# PowerDistributionBoard.net
KiCad netlist of a schematic drawn in Altium Designer
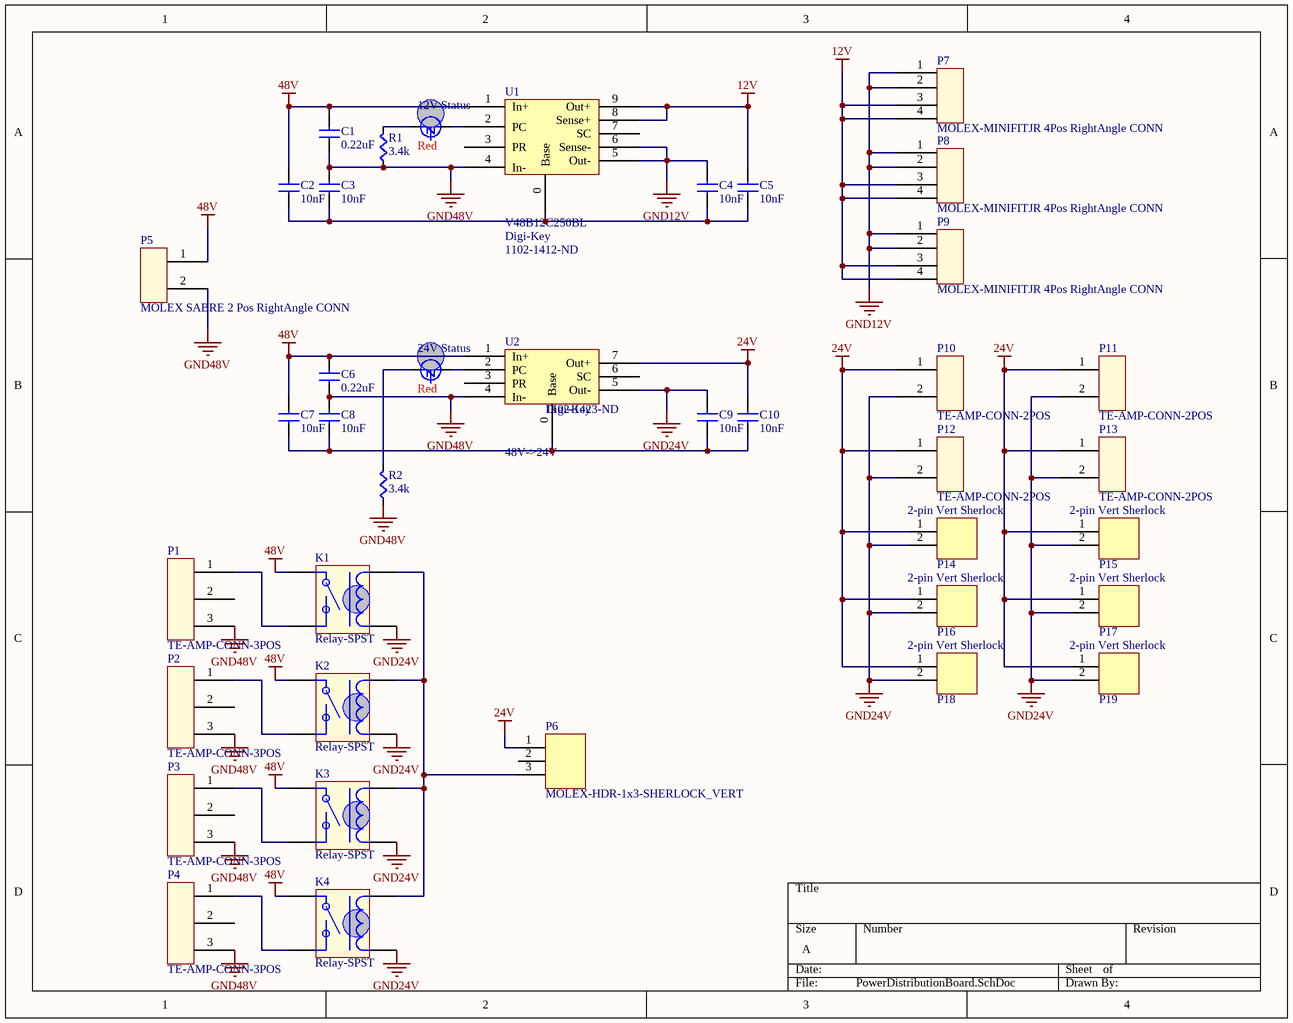
[diagram p0: PowerDistributionBoard.SchDoc]

(export (version "E")
  (design (tool "Eeschema 10.0.6"))
  (components
    (comp (ref "12V Status")
      (value "LED")
      (footprint "LED0603")
      (fields (field (name "COLOR") "Red"))
      (libsource (lib "Semiconductors") (part "LED"))
    )
    (comp (ref "24V Status")
      (value "LED")
      (footprint "LED0603")
      (fields (field (name "COLOR") "Red"))
      (libsource (lib "Semiconductors") (part "LED"))
    )
    (comp (ref "C1")
      (value "0.22uF")
      (footprint "CAP2225")
      (fields (field (name "Comment") "Cap"))
      (libsource (lib "Passives") (part "Cap"))
    )
    (comp (ref "C2")
      (value "10nF")
      (footprint "CAP2225")
      (fields (field (name "Comment") "Cap"))
      (libsource (lib "Passives") (part "Cap"))
    )
    (comp (ref "C3")
      (value "10nF")
      (footprint "CAP2225")
      (fields (field (name "Comment") "Cap"))
      (libsource (lib "Passives") (part "Cap"))
    )
    (comp (ref "C4")
      (value "10nF")
      (footprint "CAP2225")
      (fields (field (name "Comment") "Cap"))
      (libsource (lib "Passives") (part "Cap"))
    )
    (comp (ref "C5")
      (value "10nF")
      (footprint "CAP2225")
      (fields (field (name "Comment") "Cap"))
      (libsource (lib "Passives") (part "Cap"))
    )
    (comp (ref "C6")
      (value "0.22uF")
      (footprint "CAP2225")
      (fields (field (name "Comment") "Cap"))
      (libsource (lib "Passives") (part "Cap"))
    )
    (comp (ref "C7")
      (value "10nF")
      (footprint "CAP2225")
      (fields (field (name "Comment") "Cap"))
      (libsource (lib "Passives") (part "Cap"))
    )
    (comp (ref "C8")
      (value "10nF")
      (footprint "CAP2225")
      (fields (field (name "Comment") "Cap"))
      (libsource (lib "Passives") (part "Cap"))
    )
    (comp (ref "C9")
      (value "10nF")
      (footprint "CAP2225")
      (fields (field (name "Comment") "Cap"))
      (libsource (lib "Passives") (part "Cap"))
    )
    (comp (ref "C10")
      (value "10nF")
      (footprint "CAP2225")
      (fields (field (name "Comment") "Cap"))
      (libsource (lib "Passives") (part "Cap"))
    )
    (comp (ref "K1")
      (value "Relay-SPST")
      (footprint "Semiconductors:G5LE-1A4 DC24")
      (description "General Purpose Relay SPST-NO (1 Form A) 24VDC Coil Through Hole")
      (libsource (lib "Semiconductors") (part "Relay-SPST"))
    )
    (comp (ref "K2")
      (value "Relay-SPST")
      (footprint "Semiconductors:G5LE-1A4 DC24")
      (description "General Purpose Relay SPST-NO (1 Form A) 24VDC Coil Through Hole")
      (libsource (lib "Semiconductors") (part "Relay-SPST"))
    )
    (comp (ref "K3")
      (value "Relay-SPST")
      (footprint "Semiconductors:G5LE-1A4 DC24")
      (description "General Purpose Relay SPST-NO (1 Form A) 24VDC Coil Through Hole")
      (libsource (lib "Semiconductors") (part "Relay-SPST"))
    )
    (comp (ref "K4")
      (value "Relay-SPST")
      (footprint "Semiconductors:G5LE-1A4 DC24")
      (description "General Purpose Relay SPST-NO (1 Form A) 24VDC Coil Through Hole")
      (libsource (lib "Semiconductors") (part "Relay-SPST"))
    )
    (comp (ref "P1")
      (value "TE-AMP-CONN-3POS")
      (footprint "Connectors:TE AMP CONN 2POS - duplicate")
      (description "3 Positions Header Connector 0.156\" (3.96mm) Through Hole Tin")
      (libsource (lib "Connectors") (part "TE-AMP-CONN-3POS"))
    )
    (comp (ref "P2")
      (value "TE-AMP-CONN-3POS")
      (footprint "Connectors:TE AMP CONN 2POS - duplicate")
      (description "3 Positions Header Connector 0.156\" (3.96mm) Through Hole Tin")
      (libsource (lib "Connectors") (part "TE-AMP-CONN-3POS"))
    )
    (comp (ref "P3")
      (value "TE-AMP-CONN-3POS")
      (footprint "Connectors:TE AMP CONN 2POS - duplicate")
      (description "3 Positions Header Connector 0.156\" (3.96mm) Through Hole Tin")
      (libsource (lib "Connectors") (part "TE-AMP-CONN-3POS"))
    )
    (comp (ref "P4")
      (value "TE-AMP-CONN-3POS")
      (footprint "Connectors:TE AMP CONN 2POS - duplicate")
      (description "3 Positions Header Connector 0.156\" (3.96mm) Through Hole Tin")
      (libsource (lib "Connectors") (part "TE-AMP-CONN-3POS"))
    )
    (comp (ref "P5")
      (value "MOLEX SABRE 2 Pos RightAngle CONN")
      (footprint "Connectors:MOLEX-SABRE-2PIN-RA")
      (libsource (lib "Connectors") (part "MOLEX SABRE 2 Pos RightAngle CONN"))
    )
    (comp (ref "P6")
      (value "MOLEX-HDR-1x3-SHERLOCK_VERT")
      (footprint "MOLEX-HDR-1X3-SHERLOCK-VERT")
      (libsource (lib "Connectors") (part "MOLEX-HDR-1x3-SHERLOCK_VERT"))
    )
    (comp (ref "P7")
      (value "MOLEX-MINIFITJR 4Pos RightAngle CONN")
      (footprint "Connectors:MOLEX-MINIFITJR-4PINRA")
      (libsource (lib "Connectors") (part "MOLEX-MINIFITJR 4Pos RightAngle CONN"))
    )
    (comp (ref "P8")
      (value "MOLEX-MINIFITJR 4Pos RightAngle CONN")
      (footprint "Connectors:MOLEX-MINIFITJR-4PINRA")
      (libsource (lib "Connectors") (part "MOLEX-MINIFITJR 4Pos RightAngle CONN"))
    )
    (comp (ref "P9")
      (value "MOLEX-MINIFITJR 4Pos RightAngle CONN")
      (footprint "Connectors:MOLEX-MINIFITJR-4PINRA")
      (libsource (lib "Connectors") (part "MOLEX-MINIFITJR 4Pos RightAngle CONN"))
    )
    (comp (ref "P10")
      (value "TE-AMP-CONN-2POS")
      (footprint "Connectors:TE AMP CONN 2POS")
      (description "2 Positions Header Connector 0.156\" (3.96mm) Through Hole Tin")
      (libsource (lib "Connectors") (part "TE-AMP-CONN-2POS"))
    )
    (comp (ref "P11")
      (value "TE-AMP-CONN-2POS")
      (footprint "Connectors:TE AMP CONN 2POS")
      (description "2 Positions Header Connector 0.156\" (3.96mm) Through Hole Tin")
      (libsource (lib "Connectors") (part "TE-AMP-CONN-2POS"))
    )
    (comp (ref "P12")
      (value "TE-AMP-CONN-2POS")
      (footprint "Connectors:TE AMP CONN 2POS")
      (description "2 Positions Header Connector 0.156\" (3.96mm) Through Hole Tin")
      (libsource (lib "Connectors") (part "TE-AMP-CONN-2POS"))
    )
    (comp (ref "P13")
      (value "TE-AMP-CONN-2POS")
      (footprint "Connectors:TE AMP CONN 2POS")
      (description "2 Positions Header Connector 0.156\" (3.96mm) Through Hole Tin")
      (libsource (lib "Connectors") (part "TE-AMP-CONN-2POS"))
    )
    (comp (ref "P14")
      (value "2-pin Vert Sherlock")
      (footprint "MOLEX-HDR-1X2-SHERLOCK-VERT")
      (libsource (lib "Connectors") (part "MOLEX-HDR-1x2-SHERLOCK_VERT"))
    )
    (comp (ref "P15")
      (value "2-pin Vert Sherlock")
      (footprint "MOLEX-HDR-1X2-SHERLOCK-VERT")
      (libsource (lib "Connectors") (part "MOLEX-HDR-1x2-SHERLOCK_VERT"))
    )
    (comp (ref "P16")
      (value "2-pin Vert Sherlock")
      (footprint "MOLEX-HDR-1X2-SHERLOCK-VERT")
      (libsource (lib "Connectors") (part "MOLEX-HDR-1x2-SHERLOCK_VERT"))
    )
    (comp (ref "P17")
      (value "2-pin Vert Sherlock")
      (footprint "MOLEX-HDR-1X2-SHERLOCK-VERT")
      (libsource (lib "Connectors") (part "MOLEX-HDR-1x2-SHERLOCK_VERT"))
    )
    (comp (ref "P18")
      (value "2-pin Vert Sherlock")
      (footprint "MOLEX-HDR-1X2-SHERLOCK-VERT")
      (libsource (lib "Connectors") (part "MOLEX-HDR-1x2-SHERLOCK_VERT"))
    )
    (comp (ref "P19")
      (value "2-pin Vert Sherlock")
      (footprint "MOLEX-HDR-1X2-SHERLOCK-VERT")
      (libsource (lib "Connectors") (part "MOLEX-HDR-1x2-SHERLOCK_VERT"))
    )
    (comp (ref "R1")
      (value "3.4k")
      (footprint "RES0603")
      (fields (field (name "Comment") "Res"))
      (libsource (lib "Passives") (part "Res"))
    )
    (comp (ref "R2")
      (value "3.4k")
      (footprint "RES0603")
      (fields (field (name "Comment") "Res"))
      (libsource (lib "Passives") (part "Res"))
    )
    (comp (ref "U1")
      (value "V48B12C250BL")
      (footprint "ICs:FASTRAK_MINI_ONBOARD_MOUNT")
      (description "CONVERTER MOD DC/DC 12V 250W")
      (fields (field (name "SUPPLIER1") "Digi-Key") (field (name "SUPPLIER PART NUMBER 1") "1102-1412-ND"))
      (libsource (lib "ICs") (part "V48B12C250BL"))
    )
    (comp (ref "U2")
      (value "48V->24V")
      (footprint "ICs:FASTRAK_MICRO_ONBOARD_MOUNT")
      (description "CONVERTER MOD DC/DC 24V 150W")
      (fields (field (name "SUPPLIER 1") "Digi-Key") (field (name "SUPPLIER PART NUMBER 1") "1102-1423-ND"))
      (libsource (lib "ICs") (part "V48C24C150BL"))
    )
  )
  (nets
    (net (code "1") (name "12V") (class "Default")
      (node (ref "C5") (pin "1") (pinfunction "A_1") (pintype "passive"))
      (node (ref "P7") (pin "3") (pinfunction "3_3") (pintype "passive"))
      (node (ref "P7") (pin "4") (pinfunction "4_4") (pintype "passive"))
      (node (ref "P8") (pin "3") (pinfunction "3_3") (pintype "passive"))
      (node (ref "P8") (pin "4") (pinfunction "4_4") (pintype "passive"))
      (node (ref "P9") (pin "3") (pinfunction "3_3") (pintype "passive"))
      (node (ref "P9") (pin "4") (pinfunction "4_4") (pintype "passive"))
      (node (ref "U1") (pin "8") (pinfunction "Sense+_8") (pintype "passive"))
      (node (ref "U1") (pin "9") (pinfunction "Out+_9") (pintype "passive"))
    )
    (net (code "2") (name "24V") (class "Default")
      (node (ref "C10") (pin "1") (pinfunction "A_1") (pintype "passive"))
      (node (ref "P10") (pin "1") (pinfunction "1_1") (pintype "passive"))
      (node (ref "P11") (pin "1") (pinfunction "1_1") (pintype "passive"))
      (node (ref "P12") (pin "1") (pinfunction "1_1") (pintype "passive"))
      (node (ref "P13") (pin "1") (pinfunction "1_1") (pintype "passive"))
      (node (ref "P14") (pin "1") (pinfunction "1_1") (pintype "passive"))
      (node (ref "P15") (pin "1") (pinfunction "1_1") (pintype "passive"))
      (node (ref "P16") (pin "1") (pinfunction "1_1") (pintype "passive"))
      (node (ref "P17") (pin "1") (pinfunction "1_1") (pintype "passive"))
      (node (ref "P18") (pin "1") (pinfunction "1_1") (pintype "passive"))
      (node (ref "P19") (pin "1") (pinfunction "1_1") (pintype "passive"))
      (node (ref "P6") (pin "1") (pinfunction "1_1") (pintype "passive"))
      (node (ref "U2") (pin "7") (pinfunction "Out+_7") (pintype "passive"))
    )
    (net (code "3") (name "48V") (class "Default")
      (node (ref "C1") (pin "1") (pinfunction "A_1") (pintype "passive"))
      (node (ref "C2") (pin "1") (pinfunction "A_1") (pintype "passive"))
      (node (ref "C6") (pin "1") (pinfunction "A_1") (pintype "passive"))
      (node (ref "C7") (pin "1") (pinfunction "A_1") (pintype "passive"))
      (node (ref "K1") (pin "1") (pinfunction "1_1") (pintype "passive"))
      (node (ref "K2") (pin "1") (pinfunction "1_1") (pintype "passive"))
      (node (ref "K3") (pin "1") (pinfunction "1_1") (pintype "passive"))
      (node (ref "K4") (pin "1") (pinfunction "1_1") (pintype "passive"))
      (node (ref "P5") (pin "1") (pinfunction "1_1") (pintype "passive"))
      (node (ref "U1") (pin "1") (pinfunction "In+_1") (pintype "passive"))
      (node (ref "U2") (pin "1") (pinfunction "In+_1") (pintype "passive"))
    )
    (net (code "4") (name "GND12V") (class "Default")
      (node (ref "C4") (pin "1") (pinfunction "A_1") (pintype "passive"))
      (node (ref "P7") (pin "1") (pinfunction "1_1") (pintype "passive"))
      (node (ref "P7") (pin "2") (pinfunction "2_2") (pintype "passive"))
      (node (ref "P8") (pin "1") (pinfunction "1_1") (pintype "passive"))
      (node (ref "P8") (pin "2") (pinfunction "2_2") (pintype "passive"))
      (node (ref "P9") (pin "1") (pinfunction "1_1") (pintype "passive"))
      (node (ref "P9") (pin "2") (pinfunction "2_2") (pintype "passive"))
      (node (ref "U1") (pin "5") (pinfunction "Out-_5") (pintype "passive"))
      (node (ref "U1") (pin "6") (pinfunction "Sense-_6") (pintype "passive"))
    )
    (net (code "5") (name "GND24V") (class "Default")
      (node (ref "C9") (pin "1") (pinfunction "A_1") (pintype "passive"))
      (node (ref "K1") (pin "5") (pinfunction "5_5") (pintype "passive"))
      (node (ref "K2") (pin "5") (pinfunction "5_5") (pintype "passive"))
      (node (ref "K3") (pin "5") (pinfunction "5_5") (pintype "passive"))
      (node (ref "K4") (pin "5") (pinfunction "5_5") (pintype "passive"))
      (node (ref "P10") (pin "2") (pinfunction "2_2") (pintype "passive"))
      (node (ref "P11") (pin "2") (pinfunction "2_2") (pintype "passive"))
      (node (ref "P12") (pin "2") (pinfunction "2_2") (pintype "passive"))
      (node (ref "P13") (pin "2") (pinfunction "2_2") (pintype "passive"))
      (node (ref "P14") (pin "2") (pinfunction "2_2") (pintype "passive"))
      (node (ref "P15") (pin "2") (pinfunction "2_2") (pintype "passive"))
      (node (ref "P16") (pin "2") (pinfunction "2_2") (pintype "passive"))
      (node (ref "P17") (pin "2") (pinfunction "2_2") (pintype "passive"))
      (node (ref "P18") (pin "2") (pinfunction "2_2") (pintype "passive"))
      (node (ref "P19") (pin "2") (pinfunction "2_2") (pintype "passive"))
      (node (ref "U2") (pin "5") (pinfunction "Out-_5") (pintype "passive"))
    )
    (net (code "6") (name "GND48V") (class "Default")
      (node (ref "C1") (pin "2") (pinfunction "B_2") (pintype "passive"))
      (node (ref "C3") (pin "1") (pinfunction "A_1") (pintype "passive"))
      (node (ref "C6") (pin "2") (pinfunction "B_2") (pintype "passive"))
      (node (ref "C8") (pin "1") (pinfunction "A_1") (pintype "passive"))
      (node (ref "P1") (pin "3") (pinfunction "3_3") (pintype "passive"))
      (node (ref "P2") (pin "3") (pinfunction "3_3") (pintype "passive"))
      (node (ref "P3") (pin "3") (pinfunction "3_3") (pintype "passive"))
      (node (ref "P4") (pin "3") (pinfunction "3_3") (pintype "passive"))
      (node (ref "P5") (pin "2") (pinfunction "2_2") (pintype "passive"))
      (node (ref "R1") (pin "2") (pinfunction "B_2") (pintype "passive"))
      (node (ref "R2") (pin "2") (pinfunction "B_2") (pintype "passive"))
      (node (ref "U1") (pin "4") (pinfunction "In-_4") (pintype "passive"))
      (node (ref "U2") (pin "4") (pinfunction "In-_4") (pintype "passive"))
    )
    (net (code "7") (name "Net-(C2-B)") (class "Default")
      (node (ref "C2") (pin "2") (pinfunction "B_2") (pintype "passive"))
      (node (ref "C3") (pin "2") (pinfunction "B_2") (pintype "passive"))
      (node (ref "C4") (pin "2") (pinfunction "B_2") (pintype "passive"))
      (node (ref "C5") (pin "2") (pinfunction "B_2") (pintype "passive"))
      (node (ref "U1") (pin "0") (pinfunction "Base_0") (pintype "passive"))
    )
    (net (code "8") (name "Net-(C10-B)") (class "Default")
      (node (ref "C10") (pin "2") (pinfunction "B_2") (pintype "passive"))
      (node (ref "C7") (pin "2") (pinfunction "B_2") (pintype "passive"))
      (node (ref "C8") (pin "2") (pinfunction "B_2") (pintype "passive"))
      (node (ref "C9") (pin "2") (pinfunction "B_2") (pintype "passive"))
      (node (ref "U2") (pin "0") (pinfunction "Base_0") (pintype "passive"))
    )
    (net (code "9") (name "Net-(K1-Pad2)") (class "Default")
      (node (ref "K1") (pin "2") (pinfunction "2_2") (pintype "passive"))
      (node (ref "K2") (pin "2") (pinfunction "2_2") (pintype "passive"))
      (node (ref "K3") (pin "2") (pinfunction "2_2") (pintype "passive"))
      (node (ref "K4") (pin "2") (pinfunction "2_2") (pintype "passive"))
      (node (ref "P6") (pin "3") (pinfunction "3_3") (pintype "passive"))
    )
    (net (code "10") (name "Net-(K1-Pad3)") (class "Default")
      (node (ref "K1") (pin "3") (pinfunction "3_3") (pintype "passive"))
      (node (ref "P1") (pin "1") (pinfunction "1_1") (pintype "passive"))
    )
    (net (code "11") (name "Net-(K2-Pad3)") (class "Default")
      (node (ref "K2") (pin "3") (pinfunction "3_3") (pintype "passive"))
      (node (ref "P2") (pin "1") (pinfunction "1_1") (pintype "passive"))
    )
    (net (code "12") (name "Net-(K3-Pad3)") (class "Default")
      (node (ref "K3") (pin "3") (pinfunction "3_3") (pintype "passive"))
      (node (ref "P3") (pin "1") (pinfunction "1_1") (pintype "passive"))
    )
    (net (code "13") (name "Net-(K4-Pad3)") (class "Default")
      (node (ref "K4") (pin "3") (pinfunction "3_3") (pintype "passive"))
      (node (ref "P4") (pin "1") (pinfunction "1_1") (pintype "passive"))
    )
    (net (code "14") (name "Net-(R1-A)") (class "Default")
      (node (ref "12V Status") (pin "C") (pinfunction "C_C") (pintype "passive"))
      (node (ref "R1") (pin "1") (pinfunction "A_1") (pintype "passive"))
    )
    (net (code "15") (name "Net-(R2-A)") (class "Default")
      (node (ref "24V Status") (pin "C") (pinfunction "C_C") (pintype "passive"))
      (node (ref "R2") (pin "1") (pinfunction "A_1") (pintype "passive"))
    )
    (net (code "16") (name "Net-(U1-PC)") (class "Default")
      (node (ref "12V Status") (pin "A") (pinfunction "A_A") (pintype "passive"))
      (node (ref "U1") (pin "2") (pinfunction "PC_2") (pintype "passive"))
    )
    (net (code "17") (name "Net-(U2-PC)") (class "Default")
      (node (ref "24V Status") (pin "A") (pinfunction "A_A") (pintype "passive"))
      (node (ref "U2") (pin "2") (pinfunction "PC_2") (pintype "passive"))
    )
    (net (code "18") (name "unconnected-(P1-Pad2)") (class "Default")
      (node (ref "P1") (pin "2") (pinfunction "2_2") (pintype "passive"))
    )
    (net (code "19") (name "unconnected-(P2-Pad2)") (class "Default")
      (node (ref "P2") (pin "2") (pinfunction "2_2") (pintype "passive"))
    )
    (net (code "20") (name "unconnected-(P3-Pad2)") (class "Default")
      (node (ref "P3") (pin "2") (pinfunction "2_2") (pintype "passive"))
    )
    (net (code "21") (name "unconnected-(P4-Pad2)") (class "Default")
      (node (ref "P4") (pin "2") (pinfunction "2_2") (pintype "passive"))
    )
    (net (code "22") (name "unconnected-(P6-Pad2)") (class "Default")
      (node (ref "P6") (pin "2") (pinfunction "2_2") (pintype "passive"))
    )
    (net (code "23") (name "unconnected-(U1-PR-Pad3)") (class "Default")
      (node (ref "U1") (pin "3") (pinfunction "PR_3") (pintype "passive"))
    )
    (net (code "24") (name "unconnected-(U1-SC-Pad7)") (class "Default")
      (node (ref "U1") (pin "7") (pinfunction "SC_7") (pintype "passive"))
    )
    (net (code "25") (name "unconnected-(U2-PR-Pad3)") (class "Default")
      (node (ref "U2") (pin "3") (pinfunction "PR_3") (pintype "passive"))
    )
    (net (code "26") (name "unconnected-(U2-SC-Pad6)") (class "Default")
      (node (ref "U2") (pin "6") (pinfunction "SC_6") (pintype "passive"))
    )
  )
)
